# MCU.net
KiCad netlist of a schematic drawn in Altium Designer
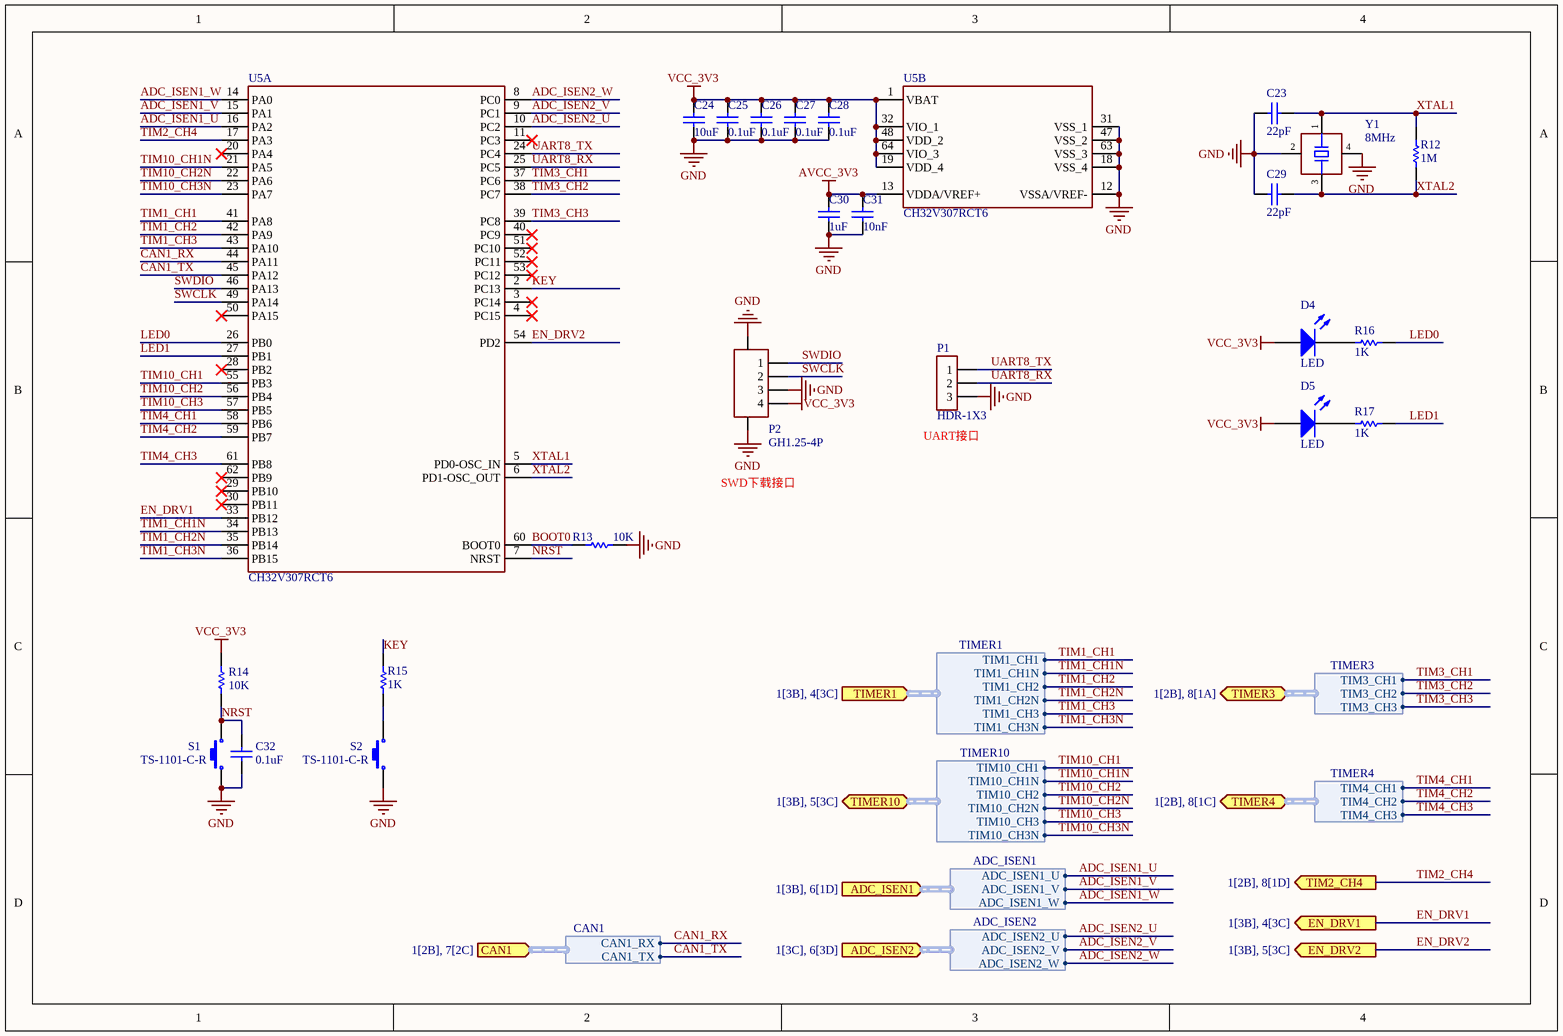
[diagram p0: MCU.SchDoc]

(export (version "E")
  (design (tool "Eeschema 10.0.6"))
  (components
    (comp (ref "C23")
      (value "22pF")
      (footprint "C0603_NS")
      (description "Capacitor")
      (fields (field (name "PUBLISHER") "Altium Limited"))
      (libsource (lib "Miscellaneous Devices") (part "Cap"))
    )
    (comp (ref "C24")
      (value "10uF")
      (footprint "C0603_NS")
      (description "Capacitor")
      (libsource (lib "Miscellaneous Devices") (part "Cap"))
    )
    (comp (ref "C25")
      (value "0.1uF")
      (footprint "C0603_NS")
      (description "Capacitor")
      (libsource (lib "Miscellaneous Devices") (part "Cap"))
    )
    (comp (ref "C26")
      (value "0.1uF")
      (footprint "C0603_NS")
      (description "Capacitor")
      (libsource (lib "Miscellaneous Devices") (part "Cap"))
    )
    (comp (ref "C27")
      (value "0.1uF")
      (footprint "C0603_NS")
      (description "Capacitor")
      (libsource (lib "Miscellaneous Devices") (part "Cap"))
    )
    (comp (ref "C28")
      (value "0.1uF")
      (footprint "C0603_NS")
      (description "Capacitor")
      (libsource (lib "Miscellaneous Devices") (part "Cap"))
    )
    (comp (ref "C29")
      (value "22pF")
      (footprint "C0603_NS")
      (description "Capacitor")
      (fields (field (name "PUBLISHER") "Altium Limited"))
      (libsource (lib "Miscellaneous Devices") (part "Cap"))
    )
    (comp (ref "C30")
      (value "1uF")
      (footprint "C0603_NS")
      (description "Capacitor")
      (libsource (lib "Miscellaneous Devices") (part "Cap"))
    )
    (comp (ref "C31")
      (value "10nF")
      (footprint "C0603_NS")
      (description "Capacitor")
      (libsource (lib "Miscellaneous Devices") (part "Cap"))
    )
    (comp (ref "C32")
      (value "0.1uF")
      (footprint "C0603_NS")
      (description "Capacitor")
      (libsource (lib "Miscellaneous Devices") (part "Cap"))
    )
    (comp (ref "D4")
      (value "LED")
      (footprint "LED0603_NS")
      (description "Typical INFRARED GaAs LED")
      (libsource (lib "Miscellaneous Devices") (part "LED0"))
    )
    (comp (ref "D5")
      (value "LED")
      (footprint "LED0603_NS")
      (description "Typical INFRARED GaAs LED")
      (libsource (lib "Miscellaneous Devices") (part "LED0"))
    )
    (comp (ref "P1")
      (value "HDR-1X3")
      (footprint "HDR2.54-WI-3P")
      (libsource (lib "my_library") (part "HDR-1X3"))
    )
    (comp (ref "P2")
      (value "GH1.25-4P")
      (footprint "A1257WR-S-4P")
      (libsource (lib "my_library") (part "Header4"))
    )
    (comp (ref "R12")
      (value "1M")
      (footprint "R0603_NS")
      (description "Resistor")
      (libsource (lib "Miscellaneous Devices") (part "Res1"))
    )
    (comp (ref "R13")
      (value "10K")
      (footprint "R0603_NS")
      (description "Resistor")
      (libsource (lib "Miscellaneous Devices") (part "Res1"))
    )
    (comp (ref "R14")
      (value "10K")
      (footprint "R0603_NS")
      (description "Resistor")
      (libsource (lib "Miscellaneous Devices") (part "Res1"))
    )
    (comp (ref "R15")
      (value "1K")
      (footprint "R0603_NS")
      (description "Resistor")
      (libsource (lib "Miscellaneous Devices") (part "Res1"))
    )
    (comp (ref "R16")
      (value "1K")
      (footprint "R0603_NS")
      (description "Resistor")
      (libsource (lib "Miscellaneous Devices") (part "Res1"))
    )
    (comp (ref "R17")
      (value "1K")
      (footprint "R0603_NS")
      (description "Resistor")
      (libsource (lib "Miscellaneous Devices") (part "Res1"))
    )
    (comp (ref "S1") (value "TS-1101-C-R") (footprint "TS-1101") (libsource (lib "my_library") (part "SW")))
    (comp (ref "S2") (value "TS-1101-C-R") (footprint "TS-1101") (libsource (lib "my_library") (part "SW")))
    (comp (ref "U5")
      (value "CH32V307RCT6")
      (footprint "LQFP64_N")
      (libsource (lib "my_library") (part "CH32V307RCT6"))
    )
    (comp (ref "Y1") (value "8MHz") (footprint "SMD-3225-4P") (libsource (lib "my_library") (part "XTAL")))
  )
  (nets
    (net (code "8") (name "/ADC_ISEN1_U") (class "Default")
      (node (ref "U5") (pin "16") (pinfunction "PA2_16") (pintype "passive"))
    )
    (net (code "9") (name "/ADC_ISEN1_V") (class "Default")
      (node (ref "U5") (pin "15") (pinfunction "PA1_15") (pintype "passive"))
    )
    (net (code "10") (name "/ADC_ISEN1_W") (class "Default")
      (node (ref "U5") (pin "14") (pinfunction "PA0_14") (pintype "passive"))
    )
    (net (code "11") (name "/ADC_ISEN2_U") (class "Default")
      (node (ref "U5") (pin "10") (pinfunction "PC2_10") (pintype "passive"))
    )
    (net (code "12") (name "/ADC_ISEN2_V") (class "Default")
      (node (ref "U5") (pin "9") (pinfunction "PC1_9") (pintype "passive"))
    )
    (net (code "13") (name "/ADC_ISEN2_W") (class "Default")
      (node (ref "U5") (pin "8") (pinfunction "PC0_8") (pintype "passive"))
    )
    (net (code "14") (name "/BOOT0") (class "Default")
      (node (ref "R13") (pin "1") (pinfunction "1_1") (pintype "passive"))
      (node (ref "U5") (pin "60") (pinfunction "BOOT0_60") (pintype "passive"))
    )
    (net (code "15") (name "/CAN1_RX") (class "Default")
      (node (ref "U5") (pin "44") (pinfunction "PA11_44") (pintype "passive"))
    )
    (net (code "16") (name "/CAN1_TX") (class "Default")
      (node (ref "U5") (pin "45") (pinfunction "PA12_45") (pintype "passive"))
    )
    (net (code "17") (name "/EN_DRV1") (class "Default")
      (node (ref "U5") (pin "33") (pinfunction "PB12_33") (pintype "passive"))
    )
    (net (code "18") (name "/EN_DRV2") (class "Default")
      (node (ref "U5") (pin "54") (pinfunction "PD2_54") (pintype "passive"))
    )
    (net (code "19") (name "/KEY") (class "Default")
      (node (ref "R15") (pin "2") (pinfunction "2_2") (pintype "passive"))
      (node (ref "U5") (pin "2") (pinfunction "PC13_2") (pintype "passive"))
    )
    (net (code "20") (name "/LED0") (class "Default")
      (node (ref "R16") (pin "2") (pinfunction "2_2") (pintype "passive"))
      (node (ref "U5") (pin "26") (pinfunction "PB0_26") (pintype "passive"))
    )
    (net (code "21") (name "/LED1") (class "Default")
      (node (ref "R17") (pin "2") (pinfunction "2_2") (pintype "passive"))
      (node (ref "U5") (pin "27") (pinfunction "PB1_27") (pintype "passive"))
    )
    (net (code "22") (name "/NRST") (class "Default")
      (node (ref "C32") (pin "2") (pinfunction "2_2") (pintype "passive"))
      (node (ref "R14") (pin "2") (pinfunction "2_2") (pintype "passive"))
      (node (ref "S1") (pin "2") (pinfunction "2_2") (pintype "passive"))
      (node (ref "U5") (pin "7") (pinfunction "NRST_7") (pintype "passive"))
    )
    (net (code "23") (name "/SWCLK") (class "Default")
      (node (ref "P2") (pin "2") (pinfunction "2_2") (pintype "passive"))
      (node (ref "U5") (pin "49") (pinfunction "PA14_49") (pintype "passive"))
    )
    (net (code "24") (name "/SWDIO") (class "Default")
      (node (ref "P2") (pin "1") (pinfunction "1_1") (pintype "passive"))
      (node (ref "U5") (pin "46") (pinfunction "PA13_46") (pintype "passive"))
    )
    (net (code "25") (name "/TIM1_CH1") (class "Default")
      (node (ref "U5") (pin "41") (pinfunction "PA8_41") (pintype "passive"))
    )
    (net (code "26") (name "/TIM1_CH1N") (class "Default")
      (node (ref "U5") (pin "34") (pinfunction "PB13_34") (pintype "passive"))
    )
    (net (code "27") (name "/TIM1_CH2") (class "Default")
      (node (ref "U5") (pin "42") (pinfunction "PA9_42") (pintype "passive"))
    )
    (net (code "28") (name "/TIM1_CH2N") (class "Default")
      (node (ref "U5") (pin "35") (pinfunction "PB14_35") (pintype "passive"))
    )
    (net (code "29") (name "/TIM1_CH3") (class "Default")
      (node (ref "U5") (pin "43") (pinfunction "PA10_43") (pintype "passive"))
    )
    (net (code "30") (name "/TIM1_CH3N") (class "Default")
      (node (ref "U5") (pin "36") (pinfunction "PB15_36") (pintype "passive"))
    )
    (net (code "31") (name "/TIM2_CH4") (class "Default")
      (node (ref "U5") (pin "17") (pinfunction "PA3_17") (pintype "passive"))
    )
    (net (code "32") (name "/TIM3_CH1") (class "Default")
      (node (ref "U5") (pin "37") (pinfunction "PC6_37") (pintype "passive"))
    )
    (net (code "33") (name "/TIM3_CH2") (class "Default")
      (node (ref "U5") (pin "38") (pinfunction "PC7_38") (pintype "passive"))
    )
    (net (code "34") (name "/TIM3_CH3") (class "Default")
      (node (ref "U5") (pin "39") (pinfunction "PC8_39") (pintype "passive"))
    )
    (net (code "35") (name "/TIM4_CH1") (class "Default")
      (node (ref "U5") (pin "58") (pinfunction "PB6_58") (pintype "passive"))
    )
    (net (code "36") (name "/TIM4_CH2") (class "Default")
      (node (ref "U5") (pin "59") (pinfunction "PB7_59") (pintype "passive"))
    )
    (net (code "37") (name "/TIM4_CH3") (class "Default")
      (node (ref "U5") (pin "61") (pinfunction "PB8_61") (pintype "passive"))
    )
    (net (code "38") (name "/TIM10_CH1") (class "Default")
      (node (ref "U5") (pin "55") (pinfunction "PB3_55") (pintype "passive"))
    )
    (net (code "39") (name "/TIM10_CH1N") (class "Default")
      (node (ref "U5") (pin "21") (pinfunction "PA5_21") (pintype "passive"))
    )
    (net (code "40") (name "/TIM10_CH2") (class "Default")
      (node (ref "U5") (pin "56") (pinfunction "PB4_56") (pintype "passive"))
    )
    (net (code "41") (name "/TIM10_CH2N") (class "Default")
      (node (ref "U5") (pin "22") (pinfunction "PA6_22") (pintype "passive"))
    )
    (net (code "42") (name "/TIM10_CH3") (class "Default")
      (node (ref "U5") (pin "57") (pinfunction "PB5_57") (pintype "passive"))
    )
    (net (code "43") (name "/TIM10_CH3N") (class "Default")
      (node (ref "U5") (pin "23") (pinfunction "PA7_23") (pintype "passive"))
    )
    (net (code "44") (name "/UART8_RX") (class "Default")
      (node (ref "P1") (pin "2") (pinfunction "2_2") (pintype "passive"))
      (node (ref "U5") (pin "25") (pinfunction "PC5_25") (pintype "passive"))
    )
    (net (code "45") (name "/UART8_TX") (class "Default")
      (node (ref "P1") (pin "1") (pinfunction "1_1") (pintype "passive"))
      (node (ref "U5") (pin "24") (pinfunction "PC4_24") (pintype "passive"))
    )
    (net (code "46") (name "/XTAL1") (class "Default")
      (node (ref "C23") (pin "2") (pinfunction "2_2") (pintype "passive"))
      (node (ref "R12") (pin "2") (pinfunction "2_2") (pintype "passive"))
      (node (ref "U5") (pin "5") (pinfunction "PD0-OSC_IN_5") (pintype "passive"))
      (node (ref "Y1") (pin "1") (pinfunction "1_1") (pintype "passive"))
    )
    (net (code "47") (name "/XTAL2") (class "Default")
      (node (ref "C29") (pin "2") (pinfunction "2_2") (pintype "passive"))
      (node (ref "R12") (pin "1") (pinfunction "1_1") (pintype "passive"))
      (node (ref "U5") (pin "6") (pinfunction "PD1-OSC_OUT_6") (pintype "passive"))
      (node (ref "Y1") (pin "3") (pinfunction "3_3") (pintype "passive"))
    )
    (net (code "55") (name "AVCC_3V3") (class "Default")
      (node (ref "C30") (pin "2") (pinfunction "2_2") (pintype "passive"))
      (node (ref "C31") (pin "2") (pinfunction "2_2") (pintype "passive"))
      (node (ref "U5") (pin "13") (pinfunction "VDDA/VREF+_13") (pintype "power_in"))
    )
    (net (code "56") (name "GND") (class "Default")
      (node (ref "C23") (pin "1") (pinfunction "1_1") (pintype "passive"))
      (node (ref "C24") (pin "1") (pinfunction "1_1") (pintype "passive"))
      (node (ref "C25") (pin "1") (pinfunction "1_1") (pintype "passive"))
      (node (ref "C26") (pin "1") (pinfunction "1_1") (pintype "passive"))
      (node (ref "C27") (pin "1") (pinfunction "1_1") (pintype "passive"))
      (node (ref "C28") (pin "1") (pinfunction "1_1") (pintype "passive"))
      (node (ref "C29") (pin "1") (pinfunction "1_1") (pintype "passive"))
      (node (ref "C30") (pin "1") (pinfunction "1_1") (pintype "passive"))
      (node (ref "C31") (pin "1") (pinfunction "1_1") (pintype "passive"))
      (node (ref "C32") (pin "1") (pinfunction "1_1") (pintype "passive"))
      (node (ref "P1") (pin "3") (pinfunction "3_3") (pintype "passive"))
      (node (ref "P2") (pin "0") (pinfunction "0_0") (pintype "passive"))
      (node (ref "P2") (pin "3") (pinfunction "3_3") (pintype "passive"))
      (node (ref "R13") (pin "2") (pinfunction "2_2") (pintype "passive"))
      (node (ref "S1") (pin "1") (pinfunction "1_1") (pintype "passive"))
      (node (ref "S2") (pin "1") (pinfunction "1_1") (pintype "passive"))
      (node (ref "U5") (pin "12") (pinfunction "VSSA/VREF-_12") (pintype "power_in"))
      (node (ref "U5") (pin "18") (pinfunction "VSS_4_18") (pintype "power_in"))
      (node (ref "U5") (pin "31") (pinfunction "VSS_1_31") (pintype "power_in"))
      (node (ref "U5") (pin "47") (pinfunction "VSS_2_47") (pintype "power_in"))
      (node (ref "U5") (pin "63") (pinfunction "VSS_3_63") (pintype "power_in"))
      (node (ref "Y1") (pin "2") (pinfunction "2_2") (pintype "passive"))
      (node (ref "Y1") (pin "4") (pinfunction "4_4") (pintype "passive"))
    )
    (net (code "57") (name "Net-(D4-K)") (class "Default")
      (node (ref "D4") (pin "2") (pinfunction "K_2") (pintype "passive"))
      (node (ref "R16") (pin "1") (pinfunction "1_1") (pintype "passive"))
    )
    (net (code "58") (name "Net-(D5-K)") (class "Default")
      (node (ref "D5") (pin "2") (pinfunction "K_2") (pintype "passive"))
      (node (ref "R17") (pin "1") (pinfunction "1_1") (pintype "passive"))
    )
    (net (code "59") (name "Net-(R15-Pad1)") (class "Default")
      (node (ref "R15") (pin "1") (pinfunction "1_1") (pintype "passive"))
      (node (ref "S2") (pin "2") (pinfunction "2_2") (pintype "passive"))
    )
    (net (code "60") (name "VCC_3V3") (class "Default")
      (node (ref "C24") (pin "2") (pinfunction "2_2") (pintype "passive"))
      (node (ref "C25") (pin "2") (pinfunction "2_2") (pintype "passive"))
      (node (ref "C26") (pin "2") (pinfunction "2_2") (pintype "passive"))
      (node (ref "C27") (pin "2") (pinfunction "2_2") (pintype "passive"))
      (node (ref "C28") (pin "2") (pinfunction "2_2") (pintype "passive"))
      (node (ref "D4") (pin "1") (pinfunction "A_1") (pintype "passive"))
      (node (ref "D5") (pin "1") (pinfunction "A_1") (pintype "passive"))
      (node (ref "P2") (pin "4") (pinfunction "4_4") (pintype "passive"))
      (node (ref "R14") (pin "1") (pinfunction "1_1") (pintype "passive"))
      (node (ref "U5") (pin "1") (pinfunction "VBAT_1") (pintype "power_in"))
      (node (ref "U5") (pin "19") (pinfunction "VDD_4_19") (pintype "power_in"))
      (node (ref "U5") (pin "32") (pinfunction "VIO_1_32") (pintype "power_in"))
      (node (ref "U5") (pin "48") (pinfunction "VDD_2_48") (pintype "power_in"))
      (node (ref "U5") (pin "64") (pinfunction "VIO_3_64") (pintype "power_in"))
    )
    (net (code "61") (name "unconnected-(U5A-PA4-Pad20)") (class "Default")
      (node (ref "U5") (pin "20") (pinfunction "PA4_20") (pintype "passive+no_connect"))
    )
    (net (code "62") (name "unconnected-(U5A-PA15-Pad50)") (class "Default")
      (node (ref "U5") (pin "50") (pinfunction "PA15_50") (pintype "passive+no_connect"))
    )
    (net (code "63") (name "unconnected-(U5A-PB2-Pad28)") (class "Default")
      (node (ref "U5") (pin "28") (pinfunction "PB2_28") (pintype "passive+no_connect"))
    )
    (net (code "64") (name "unconnected-(U5A-PB9-Pad62)") (class "Default")
      (node (ref "U5") (pin "62") (pinfunction "PB9_62") (pintype "passive+no_connect"))
    )
    (net (code "65") (name "unconnected-(U5A-PB10-Pad29)") (class "Default")
      (node (ref "U5") (pin "29") (pinfunction "PB10_29") (pintype "passive+no_connect"))
    )
    (net (code "66") (name "unconnected-(U5A-PB11-Pad30)") (class "Default")
      (node (ref "U5") (pin "30") (pinfunction "PB11_30") (pintype "passive+no_connect"))
    )
    (net (code "67") (name "unconnected-(U5A-PC3-Pad11)") (class "Default")
      (node (ref "U5") (pin "11") (pinfunction "PC3_11") (pintype "passive+no_connect"))
    )
    (net (code "68") (name "unconnected-(U5A-PC9-Pad40)") (class "Default")
      (node (ref "U5") (pin "40") (pinfunction "PC9_40") (pintype "passive+no_connect"))
    )
    (net (code "69") (name "unconnected-(U5A-PC10-Pad51)") (class "Default")
      (node (ref "U5") (pin "51") (pinfunction "PC10_51") (pintype "passive+no_connect"))
    )
    (net (code "70") (name "unconnected-(U5A-PC11-Pad52)") (class "Default")
      (node (ref "U5") (pin "52") (pinfunction "PC11_52") (pintype "passive+no_connect"))
    )
    (net (code "71") (name "unconnected-(U5A-PC12-Pad53)") (class "Default")
      (node (ref "U5") (pin "53") (pinfunction "PC12_53") (pintype "passive+no_connect"))
    )
    (net (code "72") (name "unconnected-(U5A-PC14-Pad3)") (class "Default")
      (node (ref "U5") (pin "3") (pinfunction "PC14_3") (pintype "passive+no_connect"))
    )
    (net (code "73") (name "unconnected-(U5A-PC15-Pad4)") (class "Default")
      (node (ref "U5") (pin "4") (pinfunction "PC15_4") (pintype "passive+no_connect"))
    )
  )
)
